# auxboxshield1_56_POT_systems.net
KiCad netlist of a schematic drawn in EAGLE
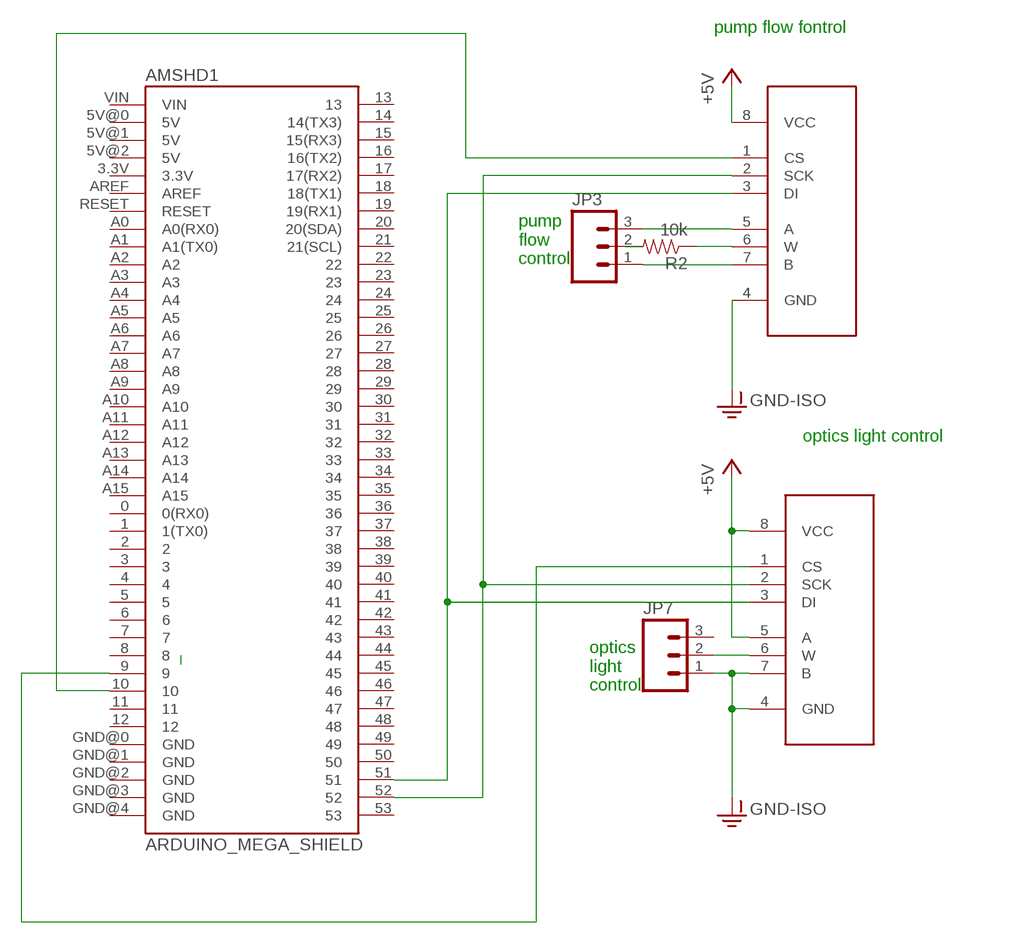
[diagram p0: schematic, sheet 1]

(export (version "E")
  (design (tool "Eeschema 10.0.6"))
  (components
    (comp (ref "AMSHD1")
      (value "ARDUINO_MEGA_SHIELD")
      (footprint "eagle-import:ARDUINO_MEGA_SHIELD")
      (libsource (lib "eagle-import") (part "ARDUINO_MEGA_SHIELD"))
    )
    (comp (ref "JP3")
      (value "M03POLAR")
      (footprint "eagle-import:MOLEX-1X3")
      (libsource (lib "eagle-import") (part "M03POLAR"))
    )
    (comp (ref "JP7")
      (value "M03POLAR")
      (footprint "eagle-import:MOLEX-1X3")
      (libsource (lib "eagle-import") (part "M03POLAR"))
    )
    (comp (ref "R2")
      (value "10k")
      (footprint "eagle-import:AXIAL-0.3")
      (libsource (lib "eagle-import") (part "10KOHM-1/4W-1%(PTH)HORIZ"))
    )
    (comp (ref "U1")
      (value "MCP41XXXDIL")
      (footprint "eagle-import:DIL-08")
      (libsource (lib "eagle-import") (part "MCP41XXXDIL"))
    )
    (comp (ref "U2")
      (value "MCP41XXXDIL")
      (footprint "eagle-import:DIL-08")
      (libsource (lib "eagle-import") (part "MCP41XXXDIL"))
    )
  )
  (nets
    (net (code "1") (name "+5V") (class "Default")
      (node (ref "U1") (pin "5") (pinfunction "A_5") (pintype "bidirectional"))
      (node (ref "U1") (pin "8") (pinfunction "VCC_8") (pintype "bidirectional"))
      (node (ref "U2") (pin "8") (pinfunction "VCC_8") (pintype "bidirectional"))
    )
    (net (code "2") (name "GND-ISO") (class "Default")
      (node (ref "JP7") (pin "1") (pinfunction "1_1") (pintype "passive"))
      (node (ref "U1") (pin "4") (pinfunction "GND_4") (pintype "bidirectional"))
      (node (ref "U1") (pin "7") (pinfunction "B_7") (pintype "bidirectional"))
      (node (ref "U2") (pin "4") (pinfunction "GND_4") (pintype "bidirectional"))
    )
    (net (code "3") (name "Net-(R2-1)") (class "Default")
      (node (ref "R2") (pin "P$1") (pinfunction "1_P$1") (pintype "passive"))
      (node (ref "U2") (pin "6") (pinfunction "W_6") (pintype "bidirectional"))
    )
    (net (code "4") (name "Net-(R2-2)") (class "Default")
      (node (ref "JP3") (pin "2") (pinfunction "2_2") (pintype "passive"))
      (node (ref "R2") (pin "P$2") (pinfunction "2_P$2") (pintype "passive"))
    )
    (net (code "5") (name "Net-(U1-CS)") (class "Default")
      (node (ref "AMSHD1") (pin "9") (pinfunction "9_9") (pintype "bidirectional"))
      (node (ref "U1") (pin "1") (pinfunction "CS_1") (pintype "bidirectional"))
    )
    (net (code "6") (name "Net-(U1-DI)") (class "Default")
      (node (ref "AMSHD1") (pin "51") (pinfunction "51_51") (pintype "bidirectional"))
      (node (ref "U1") (pin "3") (pinfunction "DI_3") (pintype "bidirectional"))
      (node (ref "U2") (pin "3") (pinfunction "DI_3") (pintype "bidirectional"))
    )
    (net (code "7") (name "Net-(U1-SCK)") (class "Default")
      (node (ref "AMSHD1") (pin "52") (pinfunction "52_52") (pintype "bidirectional"))
      (node (ref "U1") (pin "2") (pinfunction "SCK_2") (pintype "bidirectional"))
      (node (ref "U2") (pin "2") (pinfunction "SCK_2") (pintype "bidirectional"))
    )
    (net (code "8") (name "Net-(U1-W)") (class "Default")
      (node (ref "JP7") (pin "2") (pinfunction "2_2") (pintype "passive"))
      (node (ref "U1") (pin "6") (pinfunction "W_6") (pintype "bidirectional"))
    )
    (net (code "9") (name "Net-(U2-A)") (class "Default")
      (node (ref "JP3") (pin "3") (pinfunction "3_3") (pintype "passive"))
      (node (ref "U2") (pin "5") (pinfunction "A_5") (pintype "bidirectional"))
    )
    (net (code "10") (name "Net-(U2-B)") (class "Default")
      (node (ref "JP3") (pin "1") (pinfunction "1_1") (pintype "passive"))
      (node (ref "U2") (pin "7") (pinfunction "B_7") (pintype "bidirectional"))
    )
    (net (code "11") (name "Net-(U2-CS)") (class "Default")
      (node (ref "AMSHD1") (pin "10") (pinfunction "10_10") (pintype "bidirectional"))
      (node (ref "U2") (pin "1") (pinfunction "CS_1") (pintype "bidirectional"))
    )
    (net (code "12") (name "unconnected-(AMSHD1-0(RX0)-Pad0)") (class "Default")
      (node (ref "AMSHD1") (pin "0") (pinfunction "0(RX0)_0") (pintype "bidirectional"))
    )
    (net (code "13") (name "unconnected-(AMSHD1-1(TX0)-Pad1)") (class "Default")
      (node (ref "AMSHD1") (pin "1") (pinfunction "1(TX0)_1") (pintype "bidirectional"))
    )
    (net (code "14") (name "unconnected-(AMSHD1-5V-Pad5V@0)") (class "Default")
      (node (ref "AMSHD1") (pin "5V@0") (pinfunction "5V_5V@0") (pintype "bidirectional"))
    )
    (net (code "15") (name "unconnected-(AMSHD1-5V-Pad5V@1)") (class "Default")
      (node (ref "AMSHD1") (pin "5V@1") (pinfunction "5V_5V@1") (pintype "bidirectional"))
    )
    (net (code "16") (name "unconnected-(AMSHD1-5V-Pad5V@2)") (class "Default")
      (node (ref "AMSHD1") (pin "5V@2") (pinfunction "5V_5V@2") (pintype "bidirectional"))
    )
    (net (code "17") (name "unconnected-(AMSHD1-14(TX3)-Pad14)") (class "Default")
      (node (ref "AMSHD1") (pin "14") (pinfunction "14(TX3)_14") (pintype "bidirectional"))
    )
    (net (code "18") (name "unconnected-(AMSHD1-15(RX3)-Pad15)") (class "Default")
      (node (ref "AMSHD1") (pin "15") (pinfunction "15(RX3)_15") (pintype "bidirectional"))
    )
    (net (code "19") (name "unconnected-(AMSHD1-16(TX2)-Pad16)") (class "Default")
      (node (ref "AMSHD1") (pin "16") (pinfunction "16(TX2)_16") (pintype "bidirectional"))
    )
    (net (code "20") (name "unconnected-(AMSHD1-17(RX2)-Pad17)") (class "Default")
      (node (ref "AMSHD1") (pin "17") (pinfunction "17(RX2)_17") (pintype "bidirectional"))
    )
    (net (code "21") (name "unconnected-(AMSHD1-18(TX1)-Pad18)") (class "Default")
      (node (ref "AMSHD1") (pin "18") (pinfunction "18(TX1)_18") (pintype "bidirectional"))
    )
    (net (code "22") (name "unconnected-(AMSHD1-19(RX1)-Pad19)") (class "Default")
      (node (ref "AMSHD1") (pin "19") (pinfunction "19(RX1)_19") (pintype "bidirectional"))
    )
    (net (code "23") (name "unconnected-(AMSHD1-20(SDA)-Pad20)") (class "Default")
      (node (ref "AMSHD1") (pin "20") (pinfunction "20(SDA)_20") (pintype "bidirectional"))
    )
    (net (code "24") (name "unconnected-(AMSHD1-21(SCL)-Pad21)") (class "Default")
      (node (ref "AMSHD1") (pin "21") (pinfunction "21(SCL)_21") (pintype "bidirectional"))
    )
    (net (code "25") (name "unconnected-(AMSHD1-A0(RX0)-PadA0)") (class "Default")
      (node (ref "AMSHD1") (pin "A0") (pinfunction "A0(RX0)_A0") (pintype "bidirectional"))
    )
    (net (code "26") (name "unconnected-(AMSHD1-A1(TX0)-PadA1)") (class "Default")
      (node (ref "AMSHD1") (pin "A1") (pinfunction "A1(TX0)_A1") (pintype "bidirectional"))
    )
    (net (code "27") (name "unconnected-(AMSHD1-GND-PadGND@0)") (class "Default")
      (node (ref "AMSHD1") (pin "GND@0") (pinfunction "GND_GND@0") (pintype "bidirectional"))
    )
    (net (code "28") (name "unconnected-(AMSHD1-GND-PadGND@1)") (class "Default")
      (node (ref "AMSHD1") (pin "GND@1") (pinfunction "GND_GND@1") (pintype "bidirectional"))
    )
    (net (code "29") (name "unconnected-(AMSHD1-GND-PadGND@2)") (class "Default")
      (node (ref "AMSHD1") (pin "GND@2") (pinfunction "GND_GND@2") (pintype "bidirectional"))
    )
    (net (code "30") (name "unconnected-(AMSHD1-GND-PadGND@3)") (class "Default")
      (node (ref "AMSHD1") (pin "GND@3") (pinfunction "GND_GND@3") (pintype "bidirectional"))
    )
    (net (code "31") (name "unconnected-(AMSHD1-GND-PadGND@4)") (class "Default")
      (node (ref "AMSHD1") (pin "GND@4") (pinfunction "GND_GND@4") (pintype "bidirectional"))
    )
    (net (code "32") (name "unconnected-(AMSHD1-Pad2)") (class "Default")
      (node (ref "AMSHD1") (pin "2") (pinfunction "2_2") (pintype "bidirectional"))
    )
    (net (code "33") (name "unconnected-(AMSHD1-Pad3)") (class "Default")
      (node (ref "AMSHD1") (pin "3") (pinfunction "3_3") (pintype "bidirectional"))
    )
    (net (code "34") (name "unconnected-(AMSHD1-Pad3.3V)") (class "Default")
      (node (ref "AMSHD1") (pin "3.3V") (pinfunction "3.3V_3.3V") (pintype "bidirectional"))
    )
    (net (code "35") (name "unconnected-(AMSHD1-Pad4)") (class "Default")
      (node (ref "AMSHD1") (pin "4") (pinfunction "4_4") (pintype "bidirectional"))
    )
    (net (code "36") (name "unconnected-(AMSHD1-Pad5)") (class "Default")
      (node (ref "AMSHD1") (pin "5") (pinfunction "5_5") (pintype "bidirectional"))
    )
    (net (code "37") (name "unconnected-(AMSHD1-Pad6)") (class "Default")
      (node (ref "AMSHD1") (pin "6") (pinfunction "6_6") (pintype "bidirectional"))
    )
    (net (code "38") (name "unconnected-(AMSHD1-Pad7)") (class "Default")
      (node (ref "AMSHD1") (pin "7") (pinfunction "7_7") (pintype "bidirectional"))
    )
    (net (code "39") (name "unconnected-(AMSHD1-Pad8)") (class "Default")
      (node (ref "AMSHD1") (pin "8") (pinfunction "8_8") (pintype "bidirectional"))
    )
    (net (code "40") (name "unconnected-(AMSHD1-Pad11)") (class "Default")
      (node (ref "AMSHD1") (pin "11") (pinfunction "11_11") (pintype "bidirectional"))
    )
    (net (code "41") (name "unconnected-(AMSHD1-Pad12)") (class "Default")
      (node (ref "AMSHD1") (pin "12") (pinfunction "12_12") (pintype "bidirectional"))
    )
    (net (code "42") (name "unconnected-(AMSHD1-Pad13)") (class "Default")
      (node (ref "AMSHD1") (pin "13") (pinfunction "13_13") (pintype "bidirectional"))
    )
    (net (code "43") (name "unconnected-(AMSHD1-Pad22)") (class "Default")
      (node (ref "AMSHD1") (pin "22") (pinfunction "22_22") (pintype "bidirectional"))
    )
    (net (code "44") (name "unconnected-(AMSHD1-Pad23)") (class "Default")
      (node (ref "AMSHD1") (pin "23") (pinfunction "23_23") (pintype "bidirectional"))
    )
    (net (code "45") (name "unconnected-(AMSHD1-Pad24)") (class "Default")
      (node (ref "AMSHD1") (pin "24") (pinfunction "24_24") (pintype "bidirectional"))
    )
    (net (code "46") (name "unconnected-(AMSHD1-Pad25)") (class "Default")
      (node (ref "AMSHD1") (pin "25") (pinfunction "25_25") (pintype "bidirectional"))
    )
    (net (code "47") (name "unconnected-(AMSHD1-Pad26)") (class "Default")
      (node (ref "AMSHD1") (pin "26") (pinfunction "26_26") (pintype "bidirectional"))
    )
    (net (code "48") (name "unconnected-(AMSHD1-Pad27)") (class "Default")
      (node (ref "AMSHD1") (pin "27") (pinfunction "27_27") (pintype "bidirectional"))
    )
    (net (code "49") (name "unconnected-(AMSHD1-Pad28)") (class "Default")
      (node (ref "AMSHD1") (pin "28") (pinfunction "28_28") (pintype "bidirectional"))
    )
    (net (code "50") (name "unconnected-(AMSHD1-Pad29)") (class "Default")
      (node (ref "AMSHD1") (pin "29") (pinfunction "29_29") (pintype "bidirectional"))
    )
    (net (code "51") (name "unconnected-(AMSHD1-Pad30)") (class "Default")
      (node (ref "AMSHD1") (pin "30") (pinfunction "30_30") (pintype "bidirectional"))
    )
    (net (code "52") (name "unconnected-(AMSHD1-Pad31)") (class "Default")
      (node (ref "AMSHD1") (pin "31") (pinfunction "31_31") (pintype "bidirectional"))
    )
    (net (code "53") (name "unconnected-(AMSHD1-Pad32)") (class "Default")
      (node (ref "AMSHD1") (pin "32") (pinfunction "32_32") (pintype "bidirectional"))
    )
    (net (code "54") (name "unconnected-(AMSHD1-Pad33)") (class "Default")
      (node (ref "AMSHD1") (pin "33") (pinfunction "33_33") (pintype "bidirectional"))
    )
    (net (code "55") (name "unconnected-(AMSHD1-Pad34)") (class "Default")
      (node (ref "AMSHD1") (pin "34") (pinfunction "34_34") (pintype "bidirectional"))
    )
    (net (code "56") (name "unconnected-(AMSHD1-Pad35)") (class "Default")
      (node (ref "AMSHD1") (pin "35") (pinfunction "35_35") (pintype "bidirectional"))
    )
    (net (code "57") (name "unconnected-(AMSHD1-Pad36)") (class "Default")
      (node (ref "AMSHD1") (pin "36") (pinfunction "36_36") (pintype "bidirectional"))
    )
    (net (code "58") (name "unconnected-(AMSHD1-Pad37)") (class "Default")
      (node (ref "AMSHD1") (pin "37") (pinfunction "37_37") (pintype "bidirectional"))
    )
    (net (code "59") (name "unconnected-(AMSHD1-Pad38)") (class "Default")
      (node (ref "AMSHD1") (pin "38") (pinfunction "38_38") (pintype "bidirectional"))
    )
    (net (code "60") (name "unconnected-(AMSHD1-Pad39)") (class "Default")
      (node (ref "AMSHD1") (pin "39") (pinfunction "39_39") (pintype "bidirectional"))
    )
    (net (code "61") (name "unconnected-(AMSHD1-Pad40)") (class "Default")
      (node (ref "AMSHD1") (pin "40") (pinfunction "40_40") (pintype "bidirectional"))
    )
    (net (code "62") (name "unconnected-(AMSHD1-Pad41)") (class "Default")
      (node (ref "AMSHD1") (pin "41") (pinfunction "41_41") (pintype "bidirectional"))
    )
    (net (code "63") (name "unconnected-(AMSHD1-Pad42)") (class "Default")
      (node (ref "AMSHD1") (pin "42") (pinfunction "42_42") (pintype "bidirectional"))
    )
    (net (code "64") (name "unconnected-(AMSHD1-Pad43)") (class "Default")
      (node (ref "AMSHD1") (pin "43") (pinfunction "43_43") (pintype "bidirectional"))
    )
    (net (code "65") (name "unconnected-(AMSHD1-Pad44)") (class "Default")
      (node (ref "AMSHD1") (pin "44") (pinfunction "44_44") (pintype "bidirectional"))
    )
    (net (code "66") (name "unconnected-(AMSHD1-Pad45)") (class "Default")
      (node (ref "AMSHD1") (pin "45") (pinfunction "45_45") (pintype "bidirectional"))
    )
    (net (code "67") (name "unconnected-(AMSHD1-Pad46)") (class "Default")
      (node (ref "AMSHD1") (pin "46") (pinfunction "46_46") (pintype "bidirectional"))
    )
    (net (code "68") (name "unconnected-(AMSHD1-Pad47)") (class "Default")
      (node (ref "AMSHD1") (pin "47") (pinfunction "47_47") (pintype "bidirectional"))
    )
    (net (code "69") (name "unconnected-(AMSHD1-Pad48)") (class "Default")
      (node (ref "AMSHD1") (pin "48") (pinfunction "48_48") (pintype "bidirectional"))
    )
    (net (code "70") (name "unconnected-(AMSHD1-Pad49)") (class "Default")
      (node (ref "AMSHD1") (pin "49") (pinfunction "49_49") (pintype "bidirectional"))
    )
    (net (code "71") (name "unconnected-(AMSHD1-Pad50)") (class "Default")
      (node (ref "AMSHD1") (pin "50") (pinfunction "50_50") (pintype "bidirectional"))
    )
    (net (code "72") (name "unconnected-(AMSHD1-Pad53)") (class "Default")
      (node (ref "AMSHD1") (pin "53") (pinfunction "53_53") (pintype "bidirectional"))
    )
    (net (code "73") (name "unconnected-(AMSHD1-PadA2)") (class "Default")
      (node (ref "AMSHD1") (pin "A2") (pinfunction "A2_A2") (pintype "bidirectional"))
    )
    (net (code "74") (name "unconnected-(AMSHD1-PadA3)") (class "Default")
      (node (ref "AMSHD1") (pin "A3") (pinfunction "A3_A3") (pintype "bidirectional"))
    )
    (net (code "75") (name "unconnected-(AMSHD1-PadA4)") (class "Default")
      (node (ref "AMSHD1") (pin "A4") (pinfunction "A4_A4") (pintype "bidirectional"))
    )
    (net (code "76") (name "unconnected-(AMSHD1-PadA5)") (class "Default")
      (node (ref "AMSHD1") (pin "A5") (pinfunction "A5_A5") (pintype "bidirectional"))
    )
    (net (code "77") (name "unconnected-(AMSHD1-PadA6)") (class "Default")
      (node (ref "AMSHD1") (pin "A6") (pinfunction "A6_A6") (pintype "bidirectional"))
    )
    (net (code "78") (name "unconnected-(AMSHD1-PadA7)") (class "Default")
      (node (ref "AMSHD1") (pin "A7") (pinfunction "A7_A7") (pintype "bidirectional"))
    )
    (net (code "79") (name "unconnected-(AMSHD1-PadA8)") (class "Default")
      (node (ref "AMSHD1") (pin "A8") (pinfunction "A8_A8") (pintype "bidirectional"))
    )
    (net (code "80") (name "unconnected-(AMSHD1-PadA9)") (class "Default")
      (node (ref "AMSHD1") (pin "A9") (pinfunction "A9_A9") (pintype "bidirectional"))
    )
    (net (code "81") (name "unconnected-(AMSHD1-PadA10)") (class "Default")
      (node (ref "AMSHD1") (pin "A10") (pinfunction "A10_A10") (pintype "bidirectional"))
    )
    (net (code "82") (name "unconnected-(AMSHD1-PadA11)") (class "Default")
      (node (ref "AMSHD1") (pin "A11") (pinfunction "A11_A11") (pintype "bidirectional"))
    )
    (net (code "83") (name "unconnected-(AMSHD1-PadA12)") (class "Default")
      (node (ref "AMSHD1") (pin "A12") (pinfunction "A12_A12") (pintype "bidirectional"))
    )
    (net (code "84") (name "unconnected-(AMSHD1-PadA13)") (class "Default")
      (node (ref "AMSHD1") (pin "A13") (pinfunction "A13_A13") (pintype "bidirectional"))
    )
    (net (code "85") (name "unconnected-(AMSHD1-PadA14)") (class "Default")
      (node (ref "AMSHD1") (pin "A14") (pinfunction "A14_A14") (pintype "bidirectional"))
    )
    (net (code "86") (name "unconnected-(AMSHD1-PadA15)") (class "Default")
      (node (ref "AMSHD1") (pin "A15") (pinfunction "A15_A15") (pintype "bidirectional"))
    )
    (net (code "87") (name "unconnected-(AMSHD1-PadAREF)") (class "Default")
      (node (ref "AMSHD1") (pin "AREF") (pinfunction "AREF_AREF") (pintype "bidirectional"))
    )
    (net (code "88") (name "unconnected-(AMSHD1-PadRESET)") (class "Default")
      (node (ref "AMSHD1") (pin "RESET") (pinfunction "RESET_RESET") (pintype "bidirectional"))
    )
    (net (code "89") (name "unconnected-(AMSHD1-PadVIN)") (class "Default")
      (node (ref "AMSHD1") (pin "VIN") (pinfunction "VIN_VIN") (pintype "bidirectional"))
    )
    (net (code "90") (name "unconnected-(JP7-Pad3)") (class "Default")
      (node (ref "JP7") (pin "3") (pinfunction "3_3") (pintype "passive"))
    )
  )
)
